# 6_-H3_MAIN.net
KiCad netlist of a schematic drawn in Altium Designer
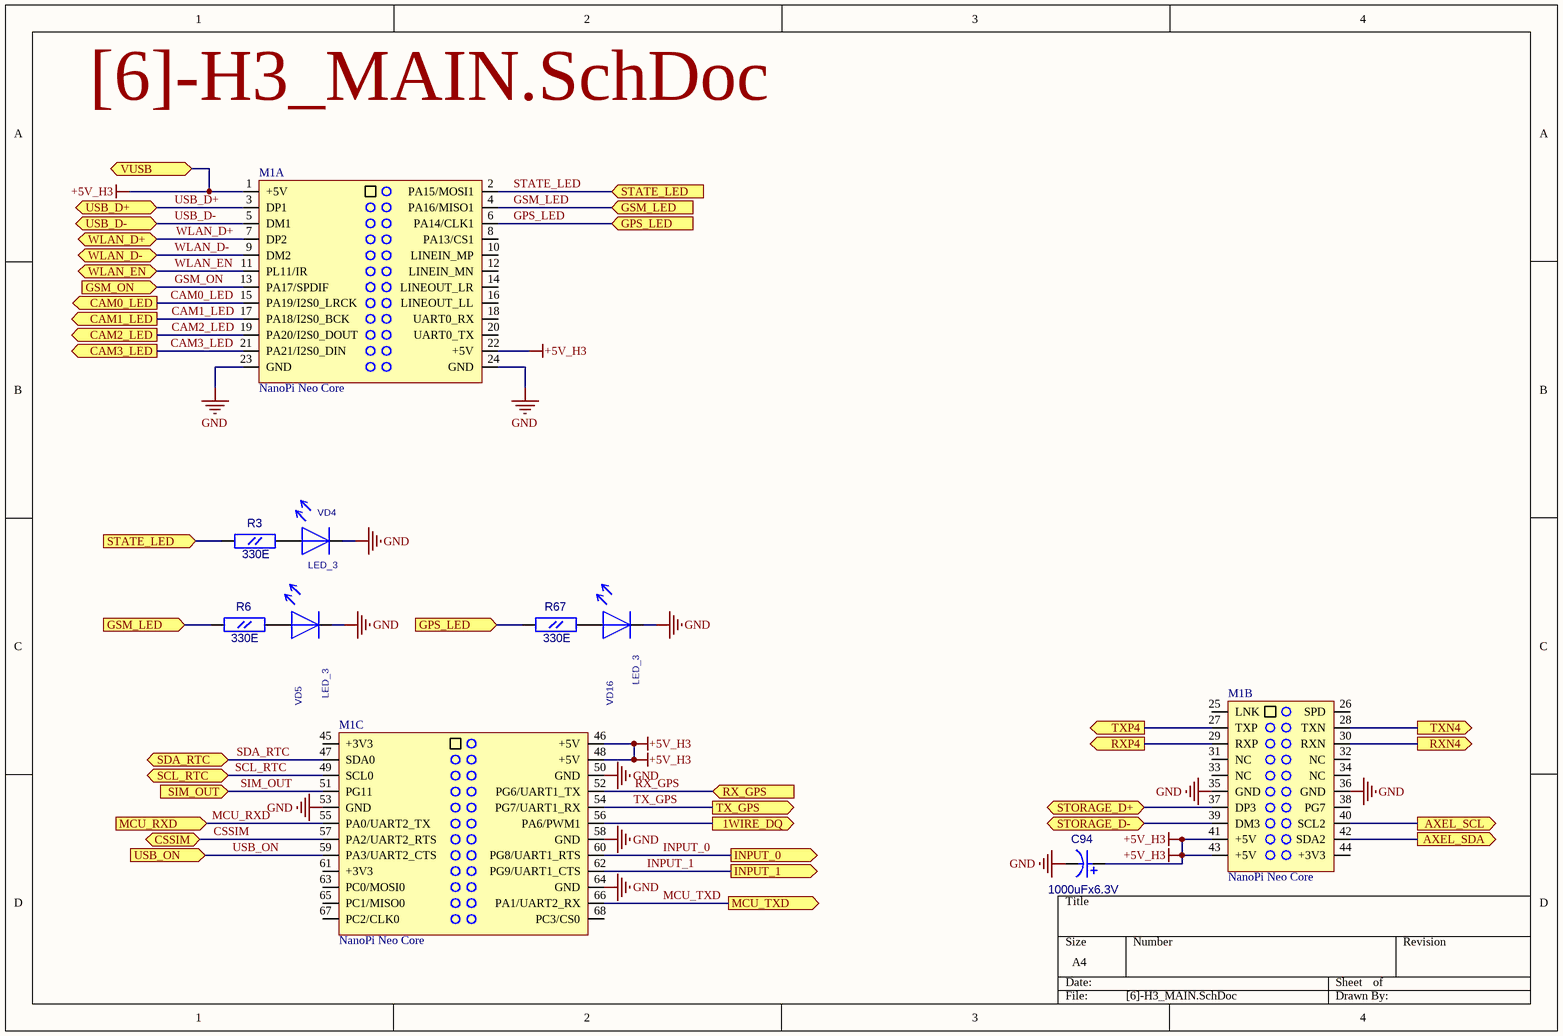
[diagram p0: [6]-H3_MAIN.SchDoc]

(export (version "E")
  (design (tool "Eeschema 10.0.6"))
  (components
    (comp (ref "C94")
      (value "1000uFx6.3V")
      (footprint "CC8X3.5")
      (description "Radial capacitor")
      (libsource (lib "fizik_lib (1)") (part "CAP_8mm"))
    )
    (comp (ref "M1")
      (value "NanoPi Neo Core")
      (footprint "NanoPiNeo_CORE")
      (description "Nano Pi Neo Core Allwinner H3 based embedded module")
      (libsource (lib "fizik_lib") (part "NanoPi Neo Core"))
    )
    (comp (ref "R3")
      (value "330E")
      (footprint "RC0603")
      (description "RC0603")
      (libsource (lib "fizik_lib (1)") (part "RC0603"))
    )
    (comp (ref "R6")
      (value "330E")
      (footprint "RC0603")
      (description "RC0603")
      (libsource (lib "fizik_lib (1)") (part "RC0603"))
    )
    (comp (ref "R67")
      (value "330E")
      (footprint "RC0603")
      (description "RC0603")
      (libsource (lib "fizik_lib (1)") (part "RC0603"))
    )
    (comp (ref "VD4") (value "LED_3") (footprint "LED3") (libsource (lib "fizik_lib (1)") (part "LED_3")))
    (comp (ref "VD5") (value "LED_3") (footprint "LED3") (libsource (lib "fizik_lib (1)") (part "LED_3")))
    (comp (ref "VD16") (value "LED_3") (footprint "LED3") (libsource (lib "fizik_lib (1)") (part "LED_3")))
  )
  (nets
    (net (code "1") (name "+5V_H3") (class "Default")
      (node (ref "C94") (pin "1") (pintype "passive"))
      (node (ref "M1") (pin "1") (pinfunction "+5V_1") (pintype "passive"))
      (node (ref "M1") (pin "22") (pinfunction "+5V_22") (pintype "passive"))
      (node (ref "M1") (pin "41") (pinfunction "+5V_41") (pintype "passive"))
      (node (ref "M1") (pin "43") (pinfunction "+5V_43") (pintype "passive"))
      (node (ref "M1") (pin "46") (pinfunction "+5V_46") (pintype "passive"))
      (node (ref "M1") (pin "48") (pinfunction "+5V_48") (pintype "passive"))
    )
    (net (code "2") (name "/1WIRE_DQ") (class "Default")
      (node (ref "M1") (pin "56") (pinfunction "PA6/PWM1_56") (pintype "passive"))
    )
    (net (code "3") (name "/AXEL_SCL") (class "Default")
      (node (ref "M1") (pin "40") (pinfunction "SCL2_40") (pintype "passive"))
    )
    (net (code "4") (name "/AXEL_SDA") (class "Default")
      (node (ref "M1") (pin "42") (pinfunction "SDA2_42") (pintype "passive"))
    )
    (net (code "5") (name "/CAM0_LED") (class "Default")
      (node (ref "M1") (pin "15") (pinfunction "PA19/I2S0_LRCK_15") (pintype "passive"))
    )
    (net (code "6") (name "/CAM1_LED") (class "Default")
      (node (ref "M1") (pin "17") (pinfunction "PA18/I2S0_BCK_17") (pintype "passive"))
    )
    (net (code "7") (name "/CAM2_LED") (class "Default")
      (node (ref "M1") (pin "19") (pinfunction "PA20/I2S0_DOUT_19") (pintype "passive"))
    )
    (net (code "8") (name "/CAM3_LED") (class "Default")
      (node (ref "M1") (pin "21") (pinfunction "PA21/I2S0_DIN_21") (pintype "passive"))
    )
    (net (code "9") (name "/CSSIM") (class "Default")
      (node (ref "M1") (pin "57") (pinfunction "PA2/UART2_RTS_57") (pintype "passive"))
    )
    (net (code "10") (name "/GPS_LED") (class "Default")
      (node (ref "M1") (pin "6") (pinfunction "PA14/CLK1_6") (pintype "passive"))
      (node (ref "R67") (pin "1") (pinfunction "A_1") (pintype "passive"))
    )
    (net (code "11") (name "/GSM_LED") (class "Default")
      (node (ref "M1") (pin "4") (pinfunction "PA16/MISO1_4") (pintype "passive"))
      (node (ref "R6") (pin "1") (pinfunction "A_1") (pintype "passive"))
    )
    (net (code "12") (name "/GSM_ON") (class "Default")
      (node (ref "M1") (pin "13") (pinfunction "PA17/SPDIF_13") (pintype "passive"))
    )
    (net (code "13") (name "/INPUT_0") (class "Default")
      (node (ref "M1") (pin "60") (pinfunction "PG8/UART1_RTS_60") (pintype "passive"))
    )
    (net (code "14") (name "/INPUT_1") (class "Default")
      (node (ref "M1") (pin "62") (pinfunction "PG9/UART1_CTS_62") (pintype "passive"))
    )
    (net (code "15") (name "/MCU_RXD") (class "Default")
      (node (ref "M1") (pin "55") (pinfunction "PA0/UART2_TX_55") (pintype "passive"))
    )
    (net (code "16") (name "/MCU_TXD") (class "Default")
      (node (ref "M1") (pin "66") (pinfunction "PA1/UART2_RX_66") (pintype "passive"))
    )
    (net (code "17") (name "/RXN4") (class "Default")
      (node (ref "M1") (pin "30") (pinfunction "RXN_30") (pintype "passive"))
    )
    (net (code "18") (name "/RXP4") (class "Default")
      (node (ref "M1") (pin "29") (pinfunction "RXP_29") (pintype "passive"))
    )
    (net (code "19") (name "/RX_GPS") (class "Default")
      (node (ref "M1") (pin "52") (pinfunction "PG6/UART1_TX_52") (pintype "passive"))
    )
    (net (code "20") (name "/SCL_RTC") (class "Default")
      (node (ref "M1") (pin "49") (pinfunction "SCL0_49") (pintype "passive"))
    )
    (net (code "21") (name "/SDA_RTC") (class "Default")
      (node (ref "M1") (pin "47") (pinfunction "SDA0_47") (pintype "passive"))
    )
    (net (code "22") (name "/SIM_OUT") (class "Default")
      (node (ref "M1") (pin "51") (pinfunction "PG11_51") (pintype "passive"))
    )
    (net (code "23") (name "/STATE_LED") (class "Default")
      (node (ref "M1") (pin "2") (pinfunction "PA15/MOSI1_2") (pintype "passive"))
      (node (ref "R3") (pin "1") (pinfunction "A_1") (pintype "passive"))
    )
    (net (code "24") (name "/STORAGE_D+") (class "Default")
      (node (ref "M1") (pin "37") (pinfunction "DP3_37") (pintype "passive"))
    )
    (net (code "25") (name "/STORAGE_D-") (class "Default")
      (node (ref "M1") (pin "39") (pinfunction "DM3_39") (pintype "passive"))
    )
    (net (code "26") (name "/TXN4") (class "Default")
      (node (ref "M1") (pin "28") (pinfunction "TXN_28") (pintype "passive"))
    )
    (net (code "27") (name "/TXP4") (class "Default")
      (node (ref "M1") (pin "27") (pinfunction "TXP_27") (pintype "passive"))
    )
    (net (code "28") (name "/TX_GPS") (class "Default")
      (node (ref "M1") (pin "54") (pinfunction "PG7/UART1_RX_54") (pintype "passive"))
    )
    (net (code "29") (name "/USB_D+") (class "Default")
      (node (ref "M1") (pin "3") (pinfunction "DP1_3") (pintype "passive"))
    )
    (net (code "30") (name "/USB_D-") (class "Default")
      (node (ref "M1") (pin "5") (pinfunction "DM1_5") (pintype "passive"))
    )
    (net (code "31") (name "/USB_ON") (class "Default")
      (node (ref "M1") (pin "59") (pinfunction "PA3/UART2_CTS_59") (pintype "passive"))
    )
    (net (code "32") (name "/WLAN_D+") (class "Default")
      (node (ref "M1") (pin "7") (pinfunction "DP2_7") (pintype "passive"))
    )
    (net (code "33") (name "/WLAN_D-") (class "Default")
      (node (ref "M1") (pin "9") (pinfunction "DM2_9") (pintype "passive"))
    )
    (net (code "34") (name "/WLAN_EN") (class "Default")
      (node (ref "M1") (pin "11") (pinfunction "PL11/IR_11") (pintype "passive"))
    )
    (net (code "35") (name "GND") (class "Default")
      (node (ref "C94") (pin "2") (pintype "passive"))
      (node (ref "M1") (pin "23") (pinfunction "GND_23") (pintype "passive"))
      (node (ref "M1") (pin "24") (pinfunction "GND_24") (pintype "passive"))
      (node (ref "M1") (pin "35") (pinfunction "GND_35") (pintype "passive"))
      (node (ref "M1") (pin "36") (pinfunction "GND_36") (pintype "passive"))
      (node (ref "M1") (pin "50") (pinfunction "GND_50") (pintype "passive"))
      (node (ref "M1") (pin "53") (pinfunction "GND_53") (pintype "passive"))
      (node (ref "M1") (pin "58") (pinfunction "GND_58") (pintype "passive"))
      (node (ref "M1") (pin "64") (pinfunction "GND_64") (pintype "passive"))
      (node (ref "VD16") (pin "1") (pintype "passive"))
      (node (ref "VD4") (pin "1") (pintype "passive"))
      (node (ref "VD5") (pin "1") (pintype "passive"))
    )
    (net (code "36") (name "Net-(R3-B)") (class "Default")
      (node (ref "R3") (pin "2") (pinfunction "B_2") (pintype "passive"))
      (node (ref "VD4") (pin "2") (pintype "passive"))
    )
    (net (code "37") (name "Net-(R6-B)") (class "Default")
      (node (ref "R6") (pin "2") (pinfunction "B_2") (pintype "passive"))
      (node (ref "VD5") (pin "2") (pintype "passive"))
    )
    (net (code "38") (name "Net-(R67-B)") (class "Default")
      (node (ref "R67") (pin "2") (pinfunction "B_2") (pintype "passive"))
      (node (ref "VD16") (pin "2") (pintype "passive"))
    )
    (net (code "39") (name "unconnected-(M1A-LINEIN_MN-Pad12)") (class "Default")
      (node (ref "M1") (pin "12") (pinfunction "LINEIN_MN_12") (pintype "passive"))
    )
    (net (code "40") (name "unconnected-(M1A-LINEIN_MP-Pad10)") (class "Default")
      (node (ref "M1") (pin "10") (pinfunction "LINEIN_MP_10") (pintype "passive"))
    )
    (net (code "41") (name "unconnected-(M1A-LINEOUT_LL-Pad16)") (class "Default")
      (node (ref "M1") (pin "16") (pinfunction "LINEOUT_LL_16") (pintype "passive"))
    )
    (net (code "42") (name "unconnected-(M1A-LINEOUT_LR-Pad14)") (class "Default")
      (node (ref "M1") (pin "14") (pinfunction "LINEOUT_LR_14") (pintype "passive"))
    )
    (net (code "43") (name "unconnected-(M1A-PA13{slash}CS1-Pad8)") (class "Default")
      (node (ref "M1") (pin "8") (pinfunction "PA13/CS1_8") (pintype "passive"))
    )
    (net (code "44") (name "unconnected-(M1A-UART0_RX-Pad18)") (class "Default")
      (node (ref "M1") (pin "18") (pinfunction "UART0_RX_18") (pintype "passive"))
    )
    (net (code "45") (name "unconnected-(M1A-UART0_TX-Pad20)") (class "Default")
      (node (ref "M1") (pin "20") (pinfunction "UART0_TX_20") (pintype "passive"))
    )
    (net (code "46") (name "unconnected-(M1B-+3V3-Pad44)") (class "Default")
      (node (ref "M1") (pin "44") (pinfunction "+3V3_44") (pintype "passive"))
    )
    (net (code "47") (name "unconnected-(M1B-LNK-Pad25)") (class "Default")
      (node (ref "M1") (pin "25") (pinfunction "LNK_25") (pintype "passive"))
    )
    (net (code "48") (name "unconnected-(M1B-NC-Pad31)") (class "Default")
      (node (ref "M1") (pin "31") (pinfunction "NC_31") (pintype "passive"))
    )
    (net (code "49") (name "unconnected-(M1B-NC-Pad32)") (class "Default")
      (node (ref "M1") (pin "32") (pinfunction "NC_32") (pintype "passive"))
    )
    (net (code "50") (name "unconnected-(M1B-NC-Pad33)") (class "Default")
      (node (ref "M1") (pin "33") (pinfunction "NC_33") (pintype "passive"))
    )
    (net (code "51") (name "unconnected-(M1B-NC-Pad34)") (class "Default")
      (node (ref "M1") (pin "34") (pinfunction "NC_34") (pintype "passive"))
    )
    (net (code "52") (name "unconnected-(M1B-PG7-Pad38)") (class "Default")
      (node (ref "M1") (pin "38") (pinfunction "PG7_38") (pintype "passive"))
    )
    (net (code "53") (name "unconnected-(M1B-SPD-Pad26)") (class "Default")
      (node (ref "M1") (pin "26") (pinfunction "SPD_26") (pintype "passive"))
    )
    (net (code "54") (name "unconnected-(M1C-+3V3-Pad45)") (class "Default")
      (node (ref "M1") (pin "45") (pinfunction "+3V3_45") (pintype "passive"))
    )
    (net (code "55") (name "unconnected-(M1C-+3V3-Pad61)") (class "Default")
      (node (ref "M1") (pin "61") (pinfunction "+3V3_61") (pintype "passive"))
    )
    (net (code "56") (name "unconnected-(M1C-PC0{slash}MOSI0-Pad63)") (class "Default")
      (node (ref "M1") (pin "63") (pinfunction "PC0/MOSI0_63") (pintype "passive"))
    )
    (net (code "57") (name "unconnected-(M1C-PC1{slash}MISO0-Pad65)") (class "Default")
      (node (ref "M1") (pin "65") (pinfunction "PC1/MISO0_65") (pintype "passive"))
    )
    (net (code "58") (name "unconnected-(M1C-PC2{slash}CLK0-Pad67)") (class "Default")
      (node (ref "M1") (pin "67") (pinfunction "PC2/CLK0_67") (pintype "passive"))
    )
    (net (code "59") (name "unconnected-(M1C-PC3{slash}CS0-Pad68)") (class "Default")
      (node (ref "M1") (pin "68") (pinfunction "PC3/CS0_68") (pintype "passive"))
    )
  )
)
